# Rapid_Feeder_Master_RS485_traces_Star.net
KiCad netlist of a schematic drawn in EAGLE
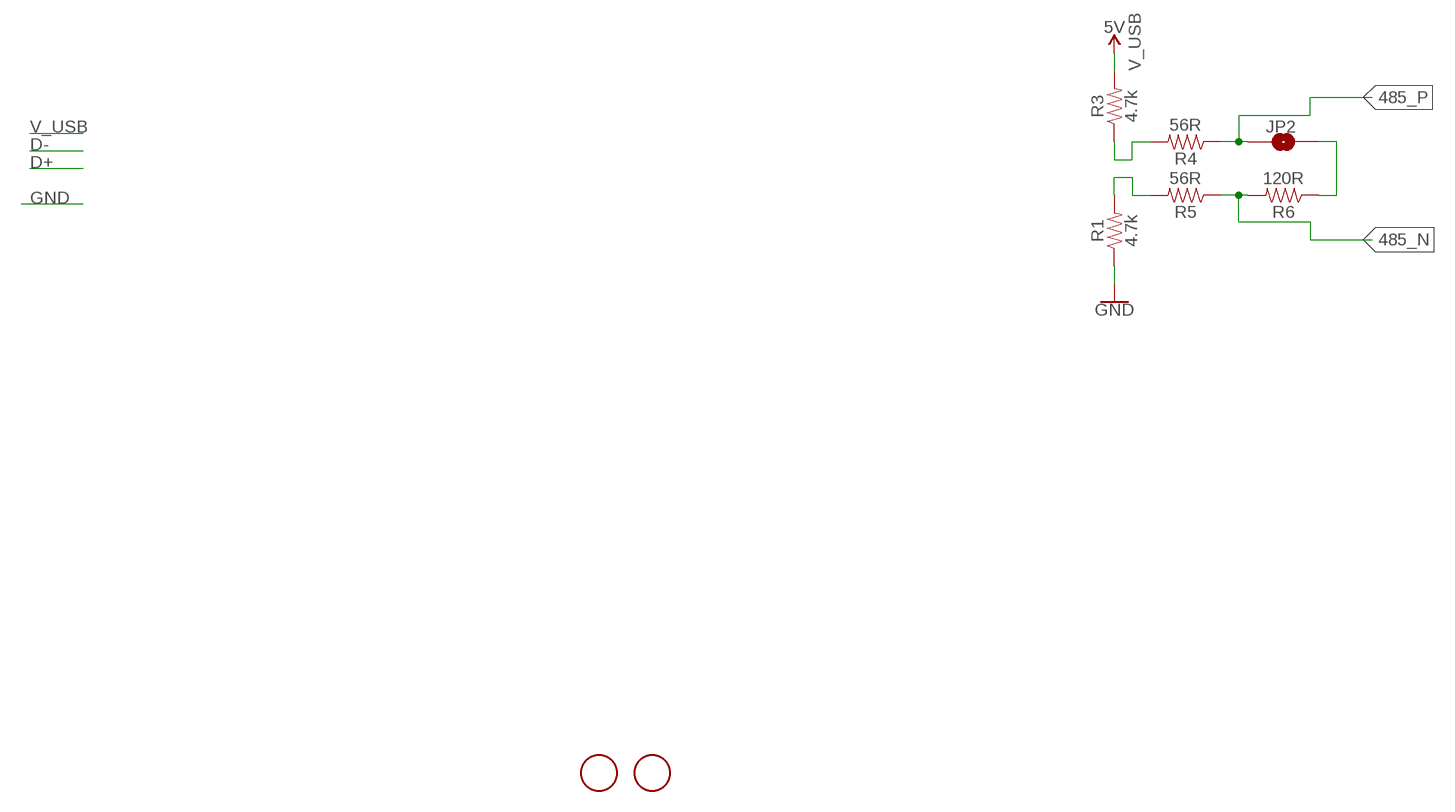
[diagram p0: schematic, sheet 1]

(export (version "E")
  (design (tool "Eeschema 10.0.6"))
  (components
    (comp (ref "JP2")
      (value "JUMPER-SMT_2_NO_NO-SILK")
      (footprint "eagle-import:SMT-JUMPER_2_NO_NO-SILK")
      (libsource (lib "eagle-import") (part "JUMPER-SMT_2_NO_NO-SILK"))
    )
    (comp (ref "R1")
      (value "4.7k")
      (footprint "eagle-import:R0603")
      (libsource (lib "eagle-import") (part "RESISTORSR0603"))
    )
    (comp (ref "R3")
      (value "4.7k")
      (footprint "eagle-import:R0603")
      (libsource (lib "eagle-import") (part "RESISTORSR0603"))
    )
    (comp (ref "R4")
      (value "56R")
      (footprint "eagle-import:R0603")
      (libsource (lib "eagle-import") (part "RESISTORSR0603"))
    )
    (comp (ref "R5")
      (value "56R")
      (footprint "eagle-import:R0603")
      (libsource (lib "eagle-import") (part "RESISTORSR0603"))
    )
    (comp (ref "R6")
      (value "120R")
      (footprint "eagle-import:R0603")
      (libsource (lib "eagle-import") (part "RESISTORSR0603"))
    )
    (comp (ref "U$1")
      (value "FIDUCIAL")
      (footprint "eagle-import:FIDUCIAL_1MM")
      (libsource (lib "eagle-import") (part "FIDUCIAL"))
    )
    (comp (ref "U$2")
      (value "FIDUCIAL")
      (footprint "eagle-import:FIDUCIAL_1MM")
      (libsource (lib "eagle-import") (part "FIDUCIAL"))
    )
  )
  (nets
    (net (code "3") (name "5V") (class "Default")
      (node (ref "R3") (pin "2") (pinfunction "2_2") (pintype "passive"))
    )
    (net (code "4") (name "485_N") (class "Default")
      (node (ref "R5") (pin "1") (pinfunction "1_1") (pintype "passive"))
      (node (ref "R6") (pin "2") (pinfunction "2_2") (pintype "passive"))
    )
    (net (code "5") (name "485_P") (class "Default")
      (node (ref "JP2") (pin "1") (pinfunction "1_1") (pintype "passive"))
      (node (ref "R4") (pin "1") (pinfunction "1_1") (pintype "passive"))
    )
    (net (code "6") (name "GND") (class "Default")
      (node (ref "R1") (pin "1") (pinfunction "1_1") (pintype "passive"))
    )
    (net (code "7") (name "Net-(JP2-Pad2)") (class "Default")
      (node (ref "JP2") (pin "2") (pinfunction "2_2") (pintype "passive"))
      (node (ref "R6") (pin "1") (pinfunction "1_1") (pintype "passive"))
    )
    (net (code "8") (name "Net-(R1-Pad2)") (class "Default")
      (node (ref "R1") (pin "2") (pinfunction "2_2") (pintype "passive"))
      (node (ref "R5") (pin "2") (pinfunction "2_2") (pintype "passive"))
    )
    (net (code "9") (name "Net-(R3-Pad1)") (class "Default")
      (node (ref "R3") (pin "1") (pinfunction "1_1") (pintype "passive"))
      (node (ref "R4") (pin "2") (pinfunction "2_2") (pintype "passive"))
    )
  )
)
